# 2-Power.net
KiCad netlist of a schematic drawn in Altium Designer
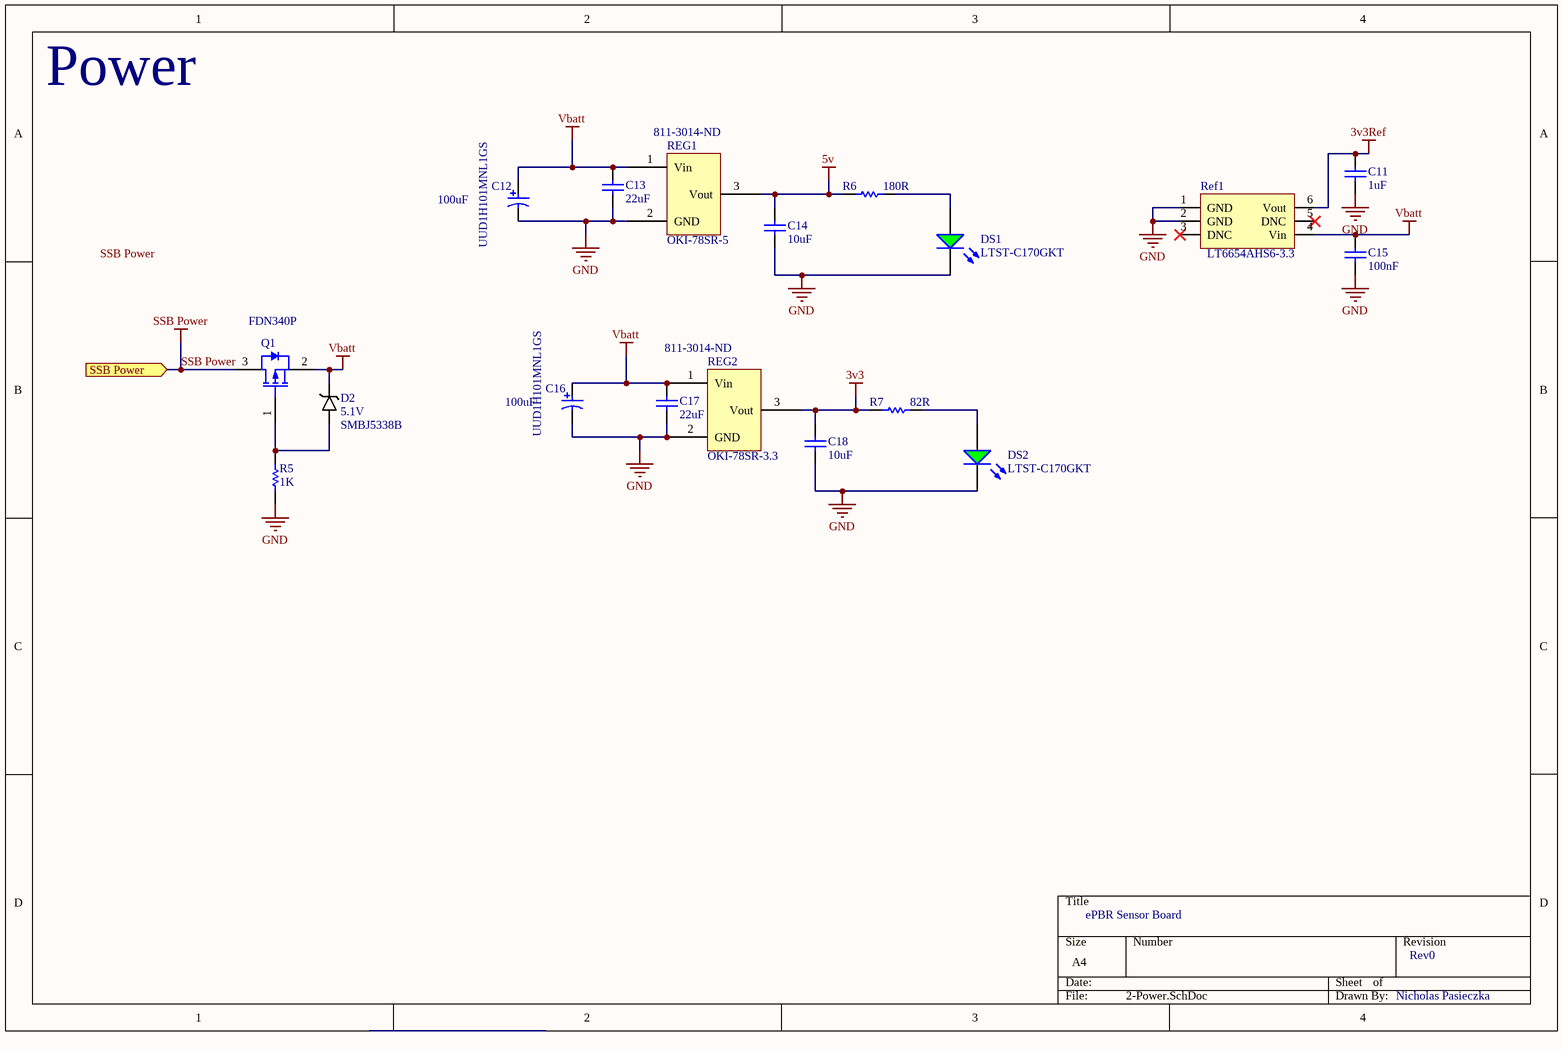
[diagram p0: 2-Power.SchDoc]

(export (version "E")
  (design (tool "Eeschema 10.0.6"))
  (components
    (comp (ref "C11")
      (value "1uF")
      (footprint "1608[0603]")
      (description "Capacitor")
      (fields
        (field (name "MANUFACTURER") "Murata Electronics North America")
        (field (name "MANUFACTURER PART NUMBER") "GRM188R61E105KA12D")
      )
      (libsource (lib "Miscellaneous Devices") (part "Cap"))
    )
    (comp (ref "C12")
      (value "UUD1H101MNL1GS")
      (footprint "NIC-CAPA2-8X10_V")
      (fields (field (name "MANUFACTURER") "Nichicon") (field (name "TOLERANCE") "±20%"))
      (libsource (lib "Altium Content Vault") (part "NIC-CAP-P-2"))
    )
    (comp (ref "C13")
      (value "22uF")
      (footprint "C1210_M")
      (description "Capacitor")
      (fields
        (field (name "MANUFACTURER") "Yageo")
        (field (name "MANUFACTURER PART NUMBER") "CC1210MKX5R8BB226")
      )
      (libsource (lib "Miscellaneous Devices") (part "Cap"))
    )
    (comp (ref "C14")
      (value "10uF")
      (footprint "C1210_M")
      (description "Capacitor")
      (fields
        (field (name "MANUFACTURER") "Yageo")
        (field (name "MANUFACTURER PART NUMBER") "CC1210ZKY5V8BB106")
      )
      (libsource (lib "Miscellaneous Devices") (part "Cap"))
    )
    (comp (ref "C15")
      (value "100nF")
      (footprint "1608[0603]")
      (description "Capacitor")
      (fields
        (field (name "MANUFACTURER") "Yageo")
        (field (name "MANUFACTURER PART NUMBER") "CC0603KRX7R9BB104")
      )
      (libsource (lib "Miscellaneous Devices") (part "Cap"))
    )
    (comp (ref "C16")
      (value "UUD1H101MNL1GS")
      (footprint "NIC-CAPA2-8X10_V")
      (fields (field (name "MANUFACTURER") "Nichicon") (field (name "TOLERANCE") "±20%"))
      (libsource (lib "Altium Content Vault") (part "NIC-CAP-P-2"))
    )
    (comp (ref "C17")
      (value "22uF")
      (footprint "C1210_M")
      (description "Capacitor")
      (fields
        (field (name "MANUFACTURER") "Yageo")
        (field (name "MANUFACTURER PART NUMBER") "CC1210MKX5R8BB226")
      )
      (libsource (lib "Miscellaneous Devices") (part "Cap"))
    )
    (comp (ref "C18")
      (value "10uF")
      (footprint "C1210_M")
      (description "Capacitor")
      (fields
        (field (name "MANUFACTURER") "Yageo")
        (field (name "MANUFACTURER PART NUMBER") "CC1210ZKY5V8BB106")
      )
      (libsource (lib "Miscellaneous Devices") (part "Cap"))
    )
    (comp (ref "D2")
      (value "Zener Diode, 5.1V, 5W SMBJ5338B")
      (footprint "DO-214AA (SMB)")
      (fields
        (field (name "POWER") "5W")
        (field (name "REVERSE VOLTAGE") "5.1V")
        (field (name "PART NUMBER") "SMBJ5338B")
      )
      (libsource (lib "VCU Library") (part "Zener Diode, 5.1V, 5W SMBJ5338B"))
    )
    (comp (ref "DS1")
      (value "LTST-C170GKT")
      (footprint "LTST-C170GKT_V")
      (description "LED Uni-Color Green, 100 mW, 120 mA, -55 to 85 degC, 2-Pin SMD, RoHS, Tape and Reel")
      (fields (field (name "MANUFACTURER") "Lite-On"))
      (libsource (lib "Altium Content Vault") (part "LED-GREEN-AK-2"))
    )
    (comp (ref "DS2")
      (value "LTST-C170GKT")
      (footprint "LTST-C170GKT_V")
      (description "LED Uni-Color Green, 100 mW, 120 mA, -55 to 85 degC, 2-Pin SMD, RoHS, Tape and Reel")
      (fields (field (name "MANUFACTURER") "Lite-On"))
      (libsource (lib "Altium Content Vault") (part "LED-GREEN-AK-2"))
    )
    (comp (ref "Q1")
      (value "FDN340P")
      (footprint "FAIR-SSOT3L-3_V")
      (fields (field (name "MANUFACTURER") "Fairchild Semiconductor"))
      (libsource (lib "Altium Content Vault") (part "PEMOS-GSD-3"))
    )
    (comp (ref "R5")
      (value "1K")
      (footprint "1608[0603]")
      (description "Resistor")
      (fields
        (field (name "MANUFACTURER") "Panasonic Electronic Components")
        (field (name "MANUFACTURER PART NUMBER") "ERJ-PA3F1001V")
      )
      (libsource (lib "Miscellaneous Devices") (part "Res1"))
    )
    (comp (ref "R6")
      (value "180R")
      (footprint "1608[0603]")
      (description "Resistor")
      (fields
        (field (name "MANUFACTURER") "Yageo")
        (field (name "MANUFACTURER PART NUMBER") "RC0603JR-07180RL")
      )
      (libsource (lib "Miscellaneous Devices") (part "Res1"))
    )
    (comp (ref "R7")
      (value "82R")
      (footprint "1608[0603]")
      (description "Resistor")
      (fields
        (field (name "MANUFACTURER") "Yageo")
        (field (name "MANUFACTURER PART NUMBER") "RC0603JR-0782RL")
      )
      (libsource (lib "Miscellaneous Devices") (part "Res1"))
    )
    (comp (ref "Ref1")
      (value "LT6654AHS6-3.3")
      (footprint "TSOT-23 S6")
      (fields
        (field (name "DIGIKEY PART NUMBER") "LT6654AHS6-3.3#TRMPBFCT-ND")
        (field (name "MANUFACTURER") "Linear Technology")
        (field (name "TOLERANCE") "±0.05%")
      )
      (libsource (lib "VCU Library") (part "LT6654AHS6-3.3"))
    )
    (comp (ref "REG1")
      (value "OKI-78SR-5")
      (footprint "OKI-78SR-5/1.5-W - Horizontal")
      (description "5V DCDC")
      (fields
        (field (name "SUPPLIER PART NUMBER 2") "811-3014-ND")
        (field (name "MANUFACTURER") "Murata Power Solutions Inc.")
        (field (name "MANUFACTURER PART NUMBER") "OKI-78SR-3.3/1.5-W36H-C")
      )
      (libsource (lib "FE Schem Lib") (part "OKI-78SR-5"))
    )
    (comp (ref "REG2")
      (value "OKI-78SR-3.3")
      (footprint "Reg - TH, 3 pin, 100 mil Pitch, VTL")
      (description "3.3V DCDC")
      (fields
        (field (name "SUPPLIER PART NUMBER 2") "811-3014-ND")
        (field (name "MANUFACTURER") "Murata Power Solutions Inc.")
        (field (name "MANUFACTURER PART NUMBER") "OKI-78SR-3.3/1.5-W36H-C")
      )
      (libsource (lib "FE Schem Lib") (part "OKI-78SR-5"))
    )
  )
  (nets
    (net (code "1") (name "3v3") (class "Default")
      (node (ref "C18") (pin "2") (pinfunction "2_2") (pintype "passive"))
      (node (ref "R7") (pin "1") (pinfunction "1_1") (pintype "passive"))
      (node (ref "REG2") (pin "3") (pinfunction "Vout_3") (pintype "passive"))
    )
    (net (code "2") (name "3v3Ref") (class "Default")
      (node (ref "C11") (pin "2") (pinfunction "2_2") (pintype "passive"))
      (node (ref "Ref1") (pin "6") (pinfunction "Vout_6") (pintype "passive"))
    )
    (net (code "3") (name "5v") (class "Default")
      (node (ref "C14") (pin "2") (pinfunction "2_2") (pintype "passive"))
      (node (ref "R6") (pin "1") (pinfunction "1_1") (pintype "passive"))
      (node (ref "REG1") (pin "3") (pinfunction "Vout_3") (pintype "passive"))
    )
    (net (code "4") (name "GND") (class "Default")
      (node (ref "C11") (pin "1") (pinfunction "1_1") (pintype "passive"))
      (node (ref "C12") (pin "2") (pinfunction "2_2") (pintype "passive"))
      (node (ref "C13") (pin "1") (pinfunction "1_1") (pintype "passive"))
      (node (ref "C14") (pin "1") (pinfunction "1_1") (pintype "passive"))
      (node (ref "C15") (pin "1") (pinfunction "1_1") (pintype "passive"))
      (node (ref "C16") (pin "2") (pinfunction "2_2") (pintype "passive"))
      (node (ref "C17") (pin "1") (pinfunction "1_1") (pintype "passive"))
      (node (ref "C18") (pin "1") (pinfunction "1_1") (pintype "passive"))
      (node (ref "DS1") (pin "2") (pinfunction "K_2") (pintype "passive"))
      (node (ref "DS2") (pin "2") (pinfunction "K_2") (pintype "passive"))
      (node (ref "R5") (pin "1") (pinfunction "1_1") (pintype "passive"))
      (node (ref "REG1") (pin "2") (pinfunction "GND_2") (pintype "passive"))
      (node (ref "REG2") (pin "2") (pinfunction "GND_2") (pintype "passive"))
      (node (ref "Ref1") (pin "1") (pinfunction "GND_1") (pintype "passive"))
      (node (ref "Ref1") (pin "2") (pinfunction "GND_2") (pintype "passive"))
    )
    (net (code "5") (name "Net-(D2-2)") (class "Default")
      (node (ref "D2") (pin "A") (pinfunction "2_A") (pintype "passive"))
      (node (ref "Q1") (pin "1") (pinfunction "GATE_1") (pintype "passive"))
      (node (ref "R5") (pin "2") (pinfunction "2_2") (pintype "passive"))
    )
    (net (code "6") (name "Net-(DS1-A)") (class "Default")
      (node (ref "DS1") (pin "1") (pinfunction "A_1") (pintype "passive"))
      (node (ref "R6") (pin "2") (pinfunction "2_2") (pintype "passive"))
    )
    (net (code "7") (name "Net-(DS2-A)") (class "Default")
      (node (ref "DS2") (pin "1") (pinfunction "A_1") (pintype "passive"))
      (node (ref "R7") (pin "2") (pinfunction "2_2") (pintype "passive"))
    )
    (net (code "8") (name "SSB Power") (class "Default")
      (node (ref "Q1") (pin "3") (pinfunction "DRAIN_3") (pintype "passive"))
    )
    (net (code "9") (name "Vbatt") (class "Default")
      (node (ref "C12") (pin "1") (pinfunction "1_1") (pintype "passive"))
      (node (ref "C13") (pin "2") (pinfunction "2_2") (pintype "passive"))
      (node (ref "C15") (pin "2") (pinfunction "2_2") (pintype "passive"))
      (node (ref "C16") (pin "1") (pinfunction "1_1") (pintype "passive"))
      (node (ref "C17") (pin "2") (pinfunction "2_2") (pintype "passive"))
      (node (ref "D2") (pin "K") (pinfunction "1_K") (pintype "passive"))
      (node (ref "Q1") (pin "2") (pinfunction "SOURCE_2") (pintype "passive"))
      (node (ref "REG1") (pin "1") (pinfunction "Vin_1") (pintype "passive"))
      (node (ref "REG2") (pin "1") (pinfunction "Vin_1") (pintype "passive"))
      (node (ref "Ref1") (pin "4") (pinfunction "Vin_4") (pintype "passive"))
    )
    (net (code "10") (name "unconnected-(Ref1-DNC-Pad3)") (class "Default")
      (node (ref "Ref1") (pin "3") (pinfunction "DNC_3") (pintype "passive+no_connect"))
    )
    (net (code "11") (name "unconnected-(Ref1-DNC-Pad5)") (class "Default")
      (node (ref "Ref1") (pin "5") (pinfunction "DNC_5") (pintype "passive+no_connect"))
    )
  )
)
